# MicroController.net
KiCad netlist of a schematic drawn in Altium Designer
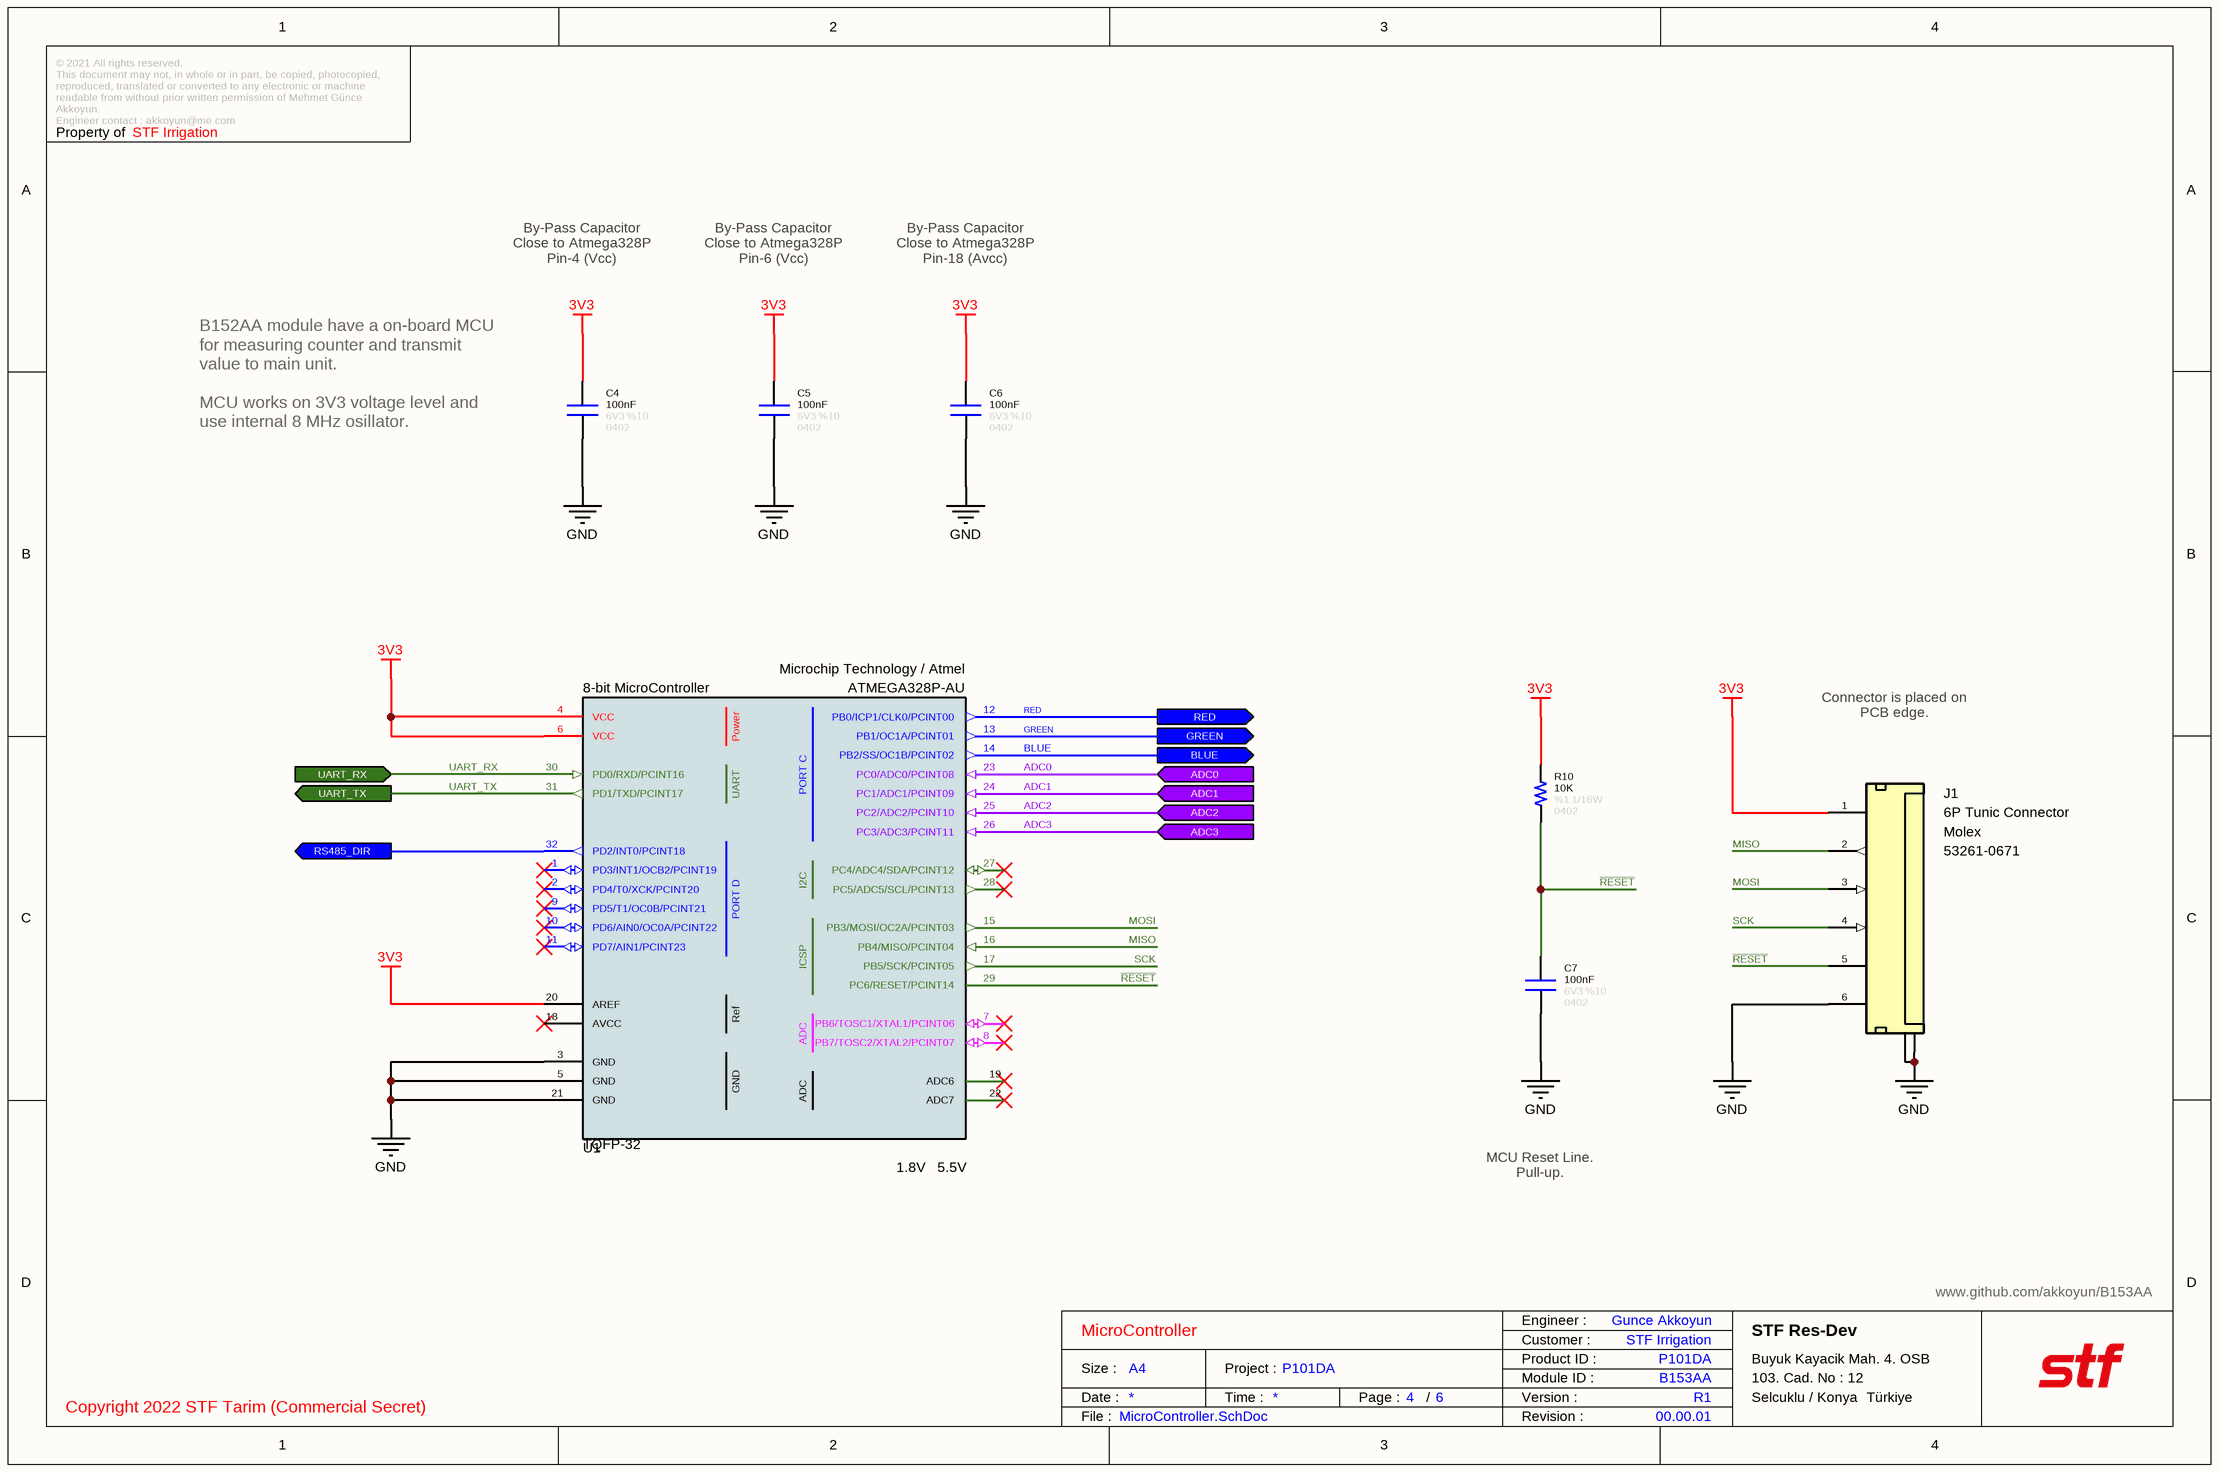
[diagram p0: MicroController.SchDoc]

(export (version "E")
  (design (tool "Eeschema 10.0.6"))
  (components
    (comp (ref "C4")
      (value "100nF")
      (footprint "CAPACITOR_0402")
      (description "Capacitor - 100nF [0402-6V3] (Ceramic)")
      (fields
        (field (name "MANUFACTURER PART NUMBER") "04026D104KAT4A")
        (field (name "TOLERANCE") "%10")
        (field (name "VOLTAGE") "6V3")
        (field (name "CASE") "0402")
        (field (name "Comment") "Capacitor - 100nF [0402] (Ceramic)")
      )
      (libsource (lib "P101DA_Library") (part "Capacitor - 100nF [0402-6V3]"))
    )
    (comp (ref "C5")
      (value "100nF")
      (footprint "CAPACITOR_0402")
      (description "Capacitor - 100nF [0402-6V3] (Ceramic)")
      (fields
        (field (name "MANUFACTURER PART NUMBER") "04026D104KAT4A")
        (field (name "TOLERANCE") "%10")
        (field (name "VOLTAGE") "6V3")
        (field (name "CASE") "0402")
        (field (name "Comment") "Capacitor - 100nF [0402] (Ceramic)")
      )
      (libsource (lib "P101DA_Library") (part "Capacitor - 100nF [0402-6V3]"))
    )
    (comp (ref "C6")
      (value "100nF")
      (footprint "CAPACITOR_0402")
      (description "Capacitor - 100nF [0402-6V3] (Ceramic)")
      (fields
        (field (name "MANUFACTURER PART NUMBER") "04026D104KAT4A")
        (field (name "TOLERANCE") "%10")
        (field (name "VOLTAGE") "6V3")
        (field (name "CASE") "0402")
        (field (name "Comment") "Capacitor - 100nF [0402] (Ceramic)")
      )
      (libsource (lib "P101DA_Library") (part "Capacitor - 100nF [0402-6V3]"))
    )
    (comp (ref "C7")
      (value "100nF")
      (footprint "CAPACITOR_0402")
      (description "Capacitor - 100nF [0402-6V3] (Ceramic)")
      (fields
        (field (name "MANUFACTURER PART NUMBER") "04026D104KAT4A")
        (field (name "TOLERANCE") "%10")
        (field (name "VOLTAGE") "6V3")
        (field (name "CASE") "0402")
        (field (name "Comment") "Capacitor - 100nF [0402] (Ceramic)")
      )
      (libsource (lib "P101DA_Library") (part "Capacitor - 100nF [0402-6V3]"))
    )
    (comp (ref "J1")
      (value "6P Tunic Connector")
      (footprint "Connector_Tunic 6P")
      (description "Mini Tunic Connector with 6P")
      (fields
        (field (name "MANUFACTURER PART NUMBER") "53261-0671")
        (field (name "MANUFACTURER NAME") "Molex")
      )
      (libsource (lib "P101DA_Library") (part "Connector - Mini Tunic 6P (1.25)"))
    )
    (comp (ref "R10")
      (value "10K")
      (footprint "RESISTOR_0402")
      (description "Thick Film Resistors - SMD 1/16 W 10 KOhm 1%")
      (fields
        (field (name "MANUFACTURER PART NUMBER") "CRCW040210K0FKED")
        (field (name "TOLERANCE") "%1")
        (field (name "CASE") "0402")
        (field (name "POWER") "1/16W")
        (field (name "Comment") "10K - 0402 - %1 - 1/16W")
      )
      (libsource (lib "P101DA_Library") (part "Resistor - 10K [0402]"))
    )
    (comp (ref "U1")
      (value "8-bit MicroController")
      (footprint "TQFN-32")
      (description "8-bit Microcontrollers - MCU 32KB In-system Flash 20MHz 1.8V-5.5V")
      (fields
        (field (name "SUPPLY VOLTAGE - MAX") "5.5V")
        (field (name "SUPPLY VOLTAGE - MIN") "1.8V")
        (field (name "MANUFACTURER NAME") "Microchip Technology / Atmel")
        (field (name "MANUFACTURER PART NUMBER") "ATMEGA328P-AU")
        (field (name "CASE") "TQFP-32")
      )
      (libsource (lib "P101DA_Library") (part "IC - ATMEGA328P-AU"))
    )
  )
  (nets
    (net (code "1") (name "/ADC0") (class "Default")
      (node (ref "U1") (pin "23") (pinfunction "PC0/ADC0/PCINT08_23") (pintype "input"))
    )
    (net (code "2") (name "/ADC1") (class "Default")
      (node (ref "U1") (pin "24") (pinfunction "PC1/ADC1/PCINT09_24") (pintype "input"))
    )
    (net (code "3") (name "/ADC2") (class "Default")
      (node (ref "U1") (pin "25") (pinfunction "PC2/ADC2/PCINT10_25") (pintype "input"))
    )
    (net (code "4") (name "/ADC3") (class "Default")
      (node (ref "U1") (pin "26") (pinfunction "PC3/ADC3/PCINT11_26") (pintype "input"))
    )
    (net (code "5") (name "/BLUE") (class "Default")
      (node (ref "U1") (pin "14") (pinfunction "PB2/SS/OC1B/PCINT02_14") (pintype "output"))
    )
    (net (code "6") (name "/GREEN") (class "Default")
      (node (ref "U1") (pin "13") (pinfunction "PB1/OC1A/PCINT01_13") (pintype "output"))
    )
    (net (code "7") (name "/MISO") (class "Default")
      (node (ref "J1") (pin "2") (pinfunction "M_DRV_2") (pintype "output"))
      (node (ref "U1") (pin "16") (pinfunction "PB4/MISO/PCINT04_16") (pintype "input"))
    )
    (net (code "8") (name "/MOSI") (class "Default")
      (node (ref "J1") (pin "3") (pinfunction "M_DRV_3") (pintype "input"))
      (node (ref "U1") (pin "15") (pinfunction "PB3/MOSI/OC2A/PCINT03_15") (pintype "output"))
    )
    (net (code "9") (name "/RED") (class "Default")
      (node (ref "U1") (pin "12") (pinfunction "PB0/ICP1/CLK0/PCINT00_12") (pintype "output"))
    )
    (net (code "10") (name "/RS485_DIR") (class "Default")
      (node (ref "U1") (pin "32") (pinfunction "PD2/INT0/PCINT18_32") (pintype "output"))
    )
    (net (code "11") (name "/SCK") (class "Default")
      (node (ref "J1") (pin "4") (pinfunction "M_DRV_4") (pintype "input"))
      (node (ref "U1") (pin "17") (pinfunction "PB5/SCK/PCINT05_17") (pintype "output"))
    )
    (net (code "12") (name "/UART_RX") (class "Default")
      (node (ref "U1") (pin "30") (pinfunction "PD0/RXD/PCINT16_30") (pintype "input"))
    )
    (net (code "13") (name "/UART_TX") (class "Default")
      (node (ref "U1") (pin "31") (pinfunction "PD1/TXD/PCINT17_31") (pintype "output"))
    )
    (net (code "14") (name "/~{RESET}") (class "Default")
      (node (ref "C7") (pin "2") (pinfunction "2_2") (pintype "passive"))
      (node (ref "J1") (pin "5") (pinfunction "M_DRV_5") (pintype "passive"))
      (node (ref "R10") (pin "1") (pinfunction "1_1") (pintype "passive"))
      (node (ref "U1") (pin "29") (pinfunction "PC6/RESET/PCINT14_29") (pintype "passive"))
    )
    (net (code "15") (name "3V3") (class "Default")
      (node (ref "C4") (pin "2") (pinfunction "2_2") (pintype "passive"))
      (node (ref "C5") (pin "2") (pinfunction "2_2") (pintype "passive"))
      (node (ref "C6") (pin "2") (pinfunction "2_2") (pintype "passive"))
      (node (ref "J1") (pin "1") (pinfunction "VBAT_1") (pintype "passive"))
      (node (ref "R10") (pin "2") (pinfunction "2_2") (pintype "passive"))
      (node (ref "U1") (pin "20") (pinfunction "AREF_20") (pintype "passive"))
      (node (ref "U1") (pin "4") (pinfunction "VCC_4") (pintype "power_in"))
      (node (ref "U1") (pin "6") (pinfunction "VCC_6") (pintype "power_in"))
    )
    (net (code "16") (name "GND") (class "Default")
      (node (ref "C4") (pin "1") (pinfunction "1_1") (pintype "passive"))
      (node (ref "C5") (pin "1") (pinfunction "1_1") (pintype "passive"))
      (node (ref "C6") (pin "1") (pinfunction "1_1") (pintype "passive"))
      (node (ref "C7") (pin "1") (pinfunction "1_1") (pintype "passive"))
      (node (ref "J1") (pin "6") (pinfunction "M_DRV_6") (pintype "passive"))
      (node (ref "J1") (pin "7") (pinfunction "GND_7") (pintype "passive"))
      (node (ref "J1") (pin "8") (pinfunction "GND_8") (pintype "passive"))
      (node (ref "U1") (pin "21") (pinfunction "GND_21") (pintype "power_in"))
      (node (ref "U1") (pin "3") (pinfunction "GND_3") (pintype "power_in"))
      (node (ref "U1") (pin "5") (pinfunction "GND_5") (pintype "power_in"))
    )
    (net (code "17") (name "unconnected-(U1-ADC6-Pad19)") (class "Default")
      (node (ref "U1") (pin "19") (pinfunction "ADC6_19") (pintype "passive+no_connect"))
    )
    (net (code "18") (name "unconnected-(U1-ADC7-Pad22)") (class "Default")
      (node (ref "U1") (pin "22") (pinfunction "ADC7_22") (pintype "passive+no_connect"))
    )
    (net (code "19") (name "unconnected-(U1-AVCC-Pad18)") (class "Default")
      (node (ref "U1") (pin "18") (pinfunction "AVCC_18") (pintype "passive+no_connect"))
    )
    (net (code "20") (name "unconnected-(U1-PB6{slash}TOSC1{slash}XTAL1{slash}PCINT06-Pad7)") (class "Default")
      (node (ref "U1") (pin "7") (pinfunction "PB6/TOSC1/XTAL1/PCINT06_7") (pintype "bidirectional+no_connect"))
    )
    (net (code "21") (name "unconnected-(U1-PB7{slash}TOSC2{slash}XTAL2{slash}PCINT07-Pad8)") (class "Default")
      (node (ref "U1") (pin "8") (pinfunction "PB7/TOSC2/XTAL2/PCINT07_8") (pintype "bidirectional+no_connect"))
    )
    (net (code "22") (name "unconnected-(U1-PC4{slash}ADC4{slash}SDA{slash}PCINT12-Pad27)") (class "Default")
      (node (ref "U1") (pin "27") (pinfunction "PC4/ADC4/SDA/PCINT12_27") (pintype "bidirectional+no_connect"))
    )
    (net (code "23") (name "unconnected-(U1-PC5{slash}ADC5{slash}SCL{slash}PCINT13-Pad28)") (class "Default")
      (node (ref "U1") (pin "28") (pinfunction "PC5/ADC5/SCL/PCINT13_28") (pintype "output+no_connect"))
    )
    (net (code "24") (name "unconnected-(U1-PD3{slash}INT1{slash}OCB2{slash}PCINT19-Pad1)") (class "Default")
      (node (ref "U1") (pin "1") (pinfunction "PD3/INT1/OCB2/PCINT19_1") (pintype "bidirectional+no_connect"))
    )
    (net (code "25") (name "unconnected-(U1-PD4{slash}T0{slash}XCK{slash}PCINT20-Pad2)") (class "Default")
      (node (ref "U1") (pin "2") (pinfunction "PD4/T0/XCK/PCINT20_2") (pintype "bidirectional+no_connect"))
    )
    (net (code "26") (name "unconnected-(U1-PD5{slash}T1{slash}OC0B{slash}PCINT21-Pad9)") (class "Default")
      (node (ref "U1") (pin "9") (pinfunction "PD5/T1/OC0B/PCINT21_9") (pintype "bidirectional+no_connect"))
    )
    (net (code "27") (name "unconnected-(U1-PD6{slash}AIN0{slash}OC0A{slash}PCINT22-Pad10)") (class "Default")
      (node (ref "U1") (pin "10") (pinfunction "PD6/AIN0/OC0A/PCINT22_10") (pintype "bidirectional+no_connect"))
    )
    (net (code "28") (name "unconnected-(U1-PD7{slash}AIN1{slash}PCINT23-Pad11)") (class "Default")
      (node (ref "U1") (pin "11") (pinfunction "PD7/AIN1/PCINT23_11") (pintype "bidirectional+no_connect"))
    )
  )
)
